# ledmatrix.net
KiCad netlist of a schematic drawn in EAGLE
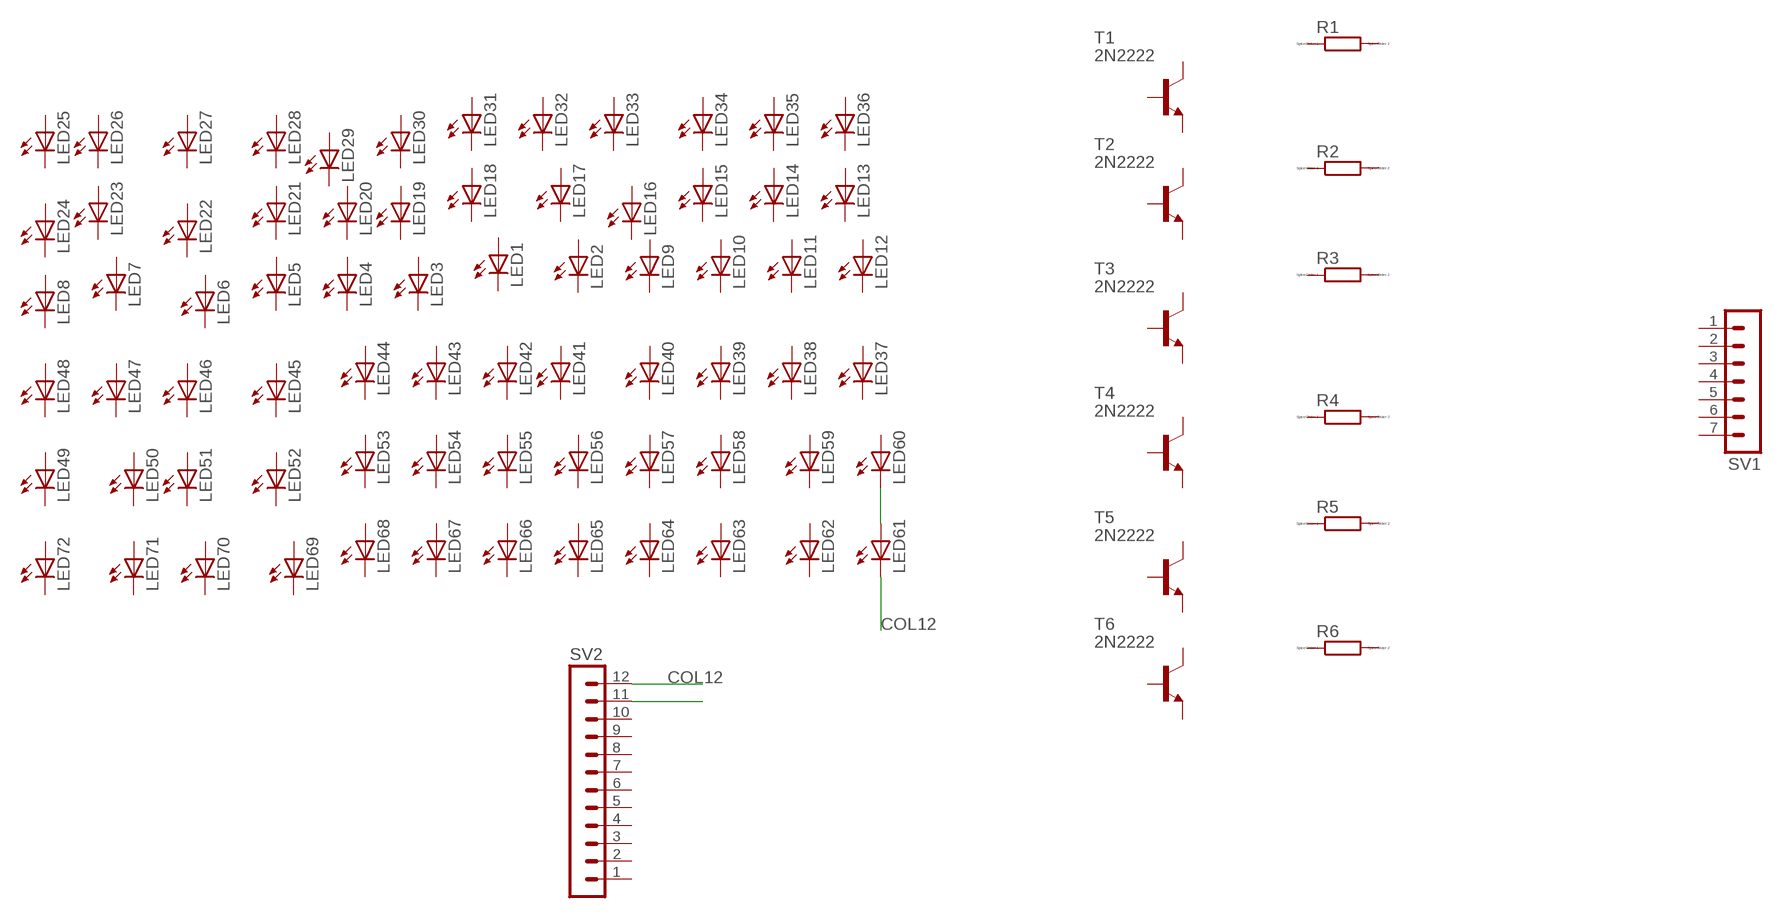
[diagram p0: schematic, sheet 1]

(export (version "E")
  (design (tool "Eeschema 10.0.6"))
  (components
    (comp (ref "LED1")
      (value "LED5MM")
      (footprint "eagle-import:LED5MM")
      (libsource (lib "eagle-import") (part "LED5MM"))
    )
    (comp (ref "LED2")
      (value "LED5MM")
      (footprint "eagle-import:LED5MM")
      (libsource (lib "eagle-import") (part "LED5MM"))
    )
    (comp (ref "LED3")
      (value "LED5MM")
      (footprint "eagle-import:LED5MM")
      (libsource (lib "eagle-import") (part "LED5MM"))
    )
    (comp (ref "LED4")
      (value "LED5MM")
      (footprint "eagle-import:LED5MM")
      (libsource (lib "eagle-import") (part "LED5MM"))
    )
    (comp (ref "LED5")
      (value "LED5MM")
      (footprint "eagle-import:LED5MM")
      (libsource (lib "eagle-import") (part "LED5MM"))
    )
    (comp (ref "LED6")
      (value "LED5MM")
      (footprint "eagle-import:LED5MM")
      (libsource (lib "eagle-import") (part "LED5MM"))
    )
    (comp (ref "LED7")
      (value "LED5MM")
      (footprint "eagle-import:LED5MM")
      (libsource (lib "eagle-import") (part "LED5MM"))
    )
    (comp (ref "LED8")
      (value "LED5MM")
      (footprint "eagle-import:LED5MM")
      (libsource (lib "eagle-import") (part "LED5MM"))
    )
    (comp (ref "LED9")
      (value "LED5MM")
      (footprint "eagle-import:LED5MM")
      (libsource (lib "eagle-import") (part "LED5MM"))
    )
    (comp (ref "LED10")
      (value "LED5MM")
      (footprint "eagle-import:LED5MM")
      (libsource (lib "eagle-import") (part "LED5MM"))
    )
    (comp (ref "LED11")
      (value "LED5MM")
      (footprint "eagle-import:LED5MM")
      (libsource (lib "eagle-import") (part "LED5MM"))
    )
    (comp (ref "LED12")
      (value "LED5MM")
      (footprint "eagle-import:LED5MM")
      (libsource (lib "eagle-import") (part "LED5MM"))
    )
    (comp (ref "LED13")
      (value "LED5MM")
      (footprint "eagle-import:LED5MM")
      (libsource (lib "eagle-import") (part "LED5MM"))
    )
    (comp (ref "LED14")
      (value "LED5MM")
      (footprint "eagle-import:LED5MM")
      (libsource (lib "eagle-import") (part "LED5MM"))
    )
    (comp (ref "LED15")
      (value "LED5MM")
      (footprint "eagle-import:LED5MM")
      (libsource (lib "eagle-import") (part "LED5MM"))
    )
    (comp (ref "LED16")
      (value "LED5MM")
      (footprint "eagle-import:LED5MM")
      (libsource (lib "eagle-import") (part "LED5MM"))
    )
    (comp (ref "LED17")
      (value "LED5MM")
      (footprint "eagle-import:LED5MM")
      (libsource (lib "eagle-import") (part "LED5MM"))
    )
    (comp (ref "LED18")
      (value "LED5MM")
      (footprint "eagle-import:LED5MM")
      (libsource (lib "eagle-import") (part "LED5MM"))
    )
    (comp (ref "LED19")
      (value "LED5MM")
      (footprint "eagle-import:LED5MM")
      (libsource (lib "eagle-import") (part "LED5MM"))
    )
    (comp (ref "LED20")
      (value "LED5MM")
      (footprint "eagle-import:LED5MM")
      (libsource (lib "eagle-import") (part "LED5MM"))
    )
    (comp (ref "LED21")
      (value "LED5MM")
      (footprint "eagle-import:LED5MM")
      (libsource (lib "eagle-import") (part "LED5MM"))
    )
    (comp (ref "LED22")
      (value "LED5MM")
      (footprint "eagle-import:LED5MM")
      (libsource (lib "eagle-import") (part "LED5MM"))
    )
    (comp (ref "LED23")
      (value "LED5MM")
      (footprint "eagle-import:LED5MM")
      (libsource (lib "eagle-import") (part "LED5MM"))
    )
    (comp (ref "LED24")
      (value "LED5MM")
      (footprint "eagle-import:LED5MM")
      (libsource (lib "eagle-import") (part "LED5MM"))
    )
    (comp (ref "LED25")
      (value "LED5MM")
      (footprint "eagle-import:LED5MM")
      (libsource (lib "eagle-import") (part "LED5MM"))
    )
    (comp (ref "LED26")
      (value "LED5MM")
      (footprint "eagle-import:LED5MM")
      (libsource (lib "eagle-import") (part "LED5MM"))
    )
    (comp (ref "LED27")
      (value "LED5MM")
      (footprint "eagle-import:LED5MM")
      (libsource (lib "eagle-import") (part "LED5MM"))
    )
    (comp (ref "LED28")
      (value "LED5MM")
      (footprint "eagle-import:LED5MM")
      (libsource (lib "eagle-import") (part "LED5MM"))
    )
    (comp (ref "LED29")
      (value "LED5MM")
      (footprint "eagle-import:LED5MM")
      (libsource (lib "eagle-import") (part "LED5MM"))
    )
    (comp (ref "LED30")
      (value "LED5MM")
      (footprint "eagle-import:LED5MM")
      (libsource (lib "eagle-import") (part "LED5MM"))
    )
    (comp (ref "LED31")
      (value "LED5MM")
      (footprint "eagle-import:LED5MM")
      (libsource (lib "eagle-import") (part "LED5MM"))
    )
    (comp (ref "LED32")
      (value "LED5MM")
      (footprint "eagle-import:LED5MM")
      (libsource (lib "eagle-import") (part "LED5MM"))
    )
    (comp (ref "LED33")
      (value "LED5MM")
      (footprint "eagle-import:LED5MM")
      (libsource (lib "eagle-import") (part "LED5MM"))
    )
    (comp (ref "LED34")
      (value "LED5MM")
      (footprint "eagle-import:LED5MM")
      (libsource (lib "eagle-import") (part "LED5MM"))
    )
    (comp (ref "LED35")
      (value "LED5MM")
      (footprint "eagle-import:LED5MM")
      (libsource (lib "eagle-import") (part "LED5MM"))
    )
    (comp (ref "LED36")
      (value "LED5MM")
      (footprint "eagle-import:LED5MM")
      (libsource (lib "eagle-import") (part "LED5MM"))
    )
    (comp (ref "LED37")
      (value "LED5MM")
      (footprint "eagle-import:LED5MM")
      (libsource (lib "eagle-import") (part "LED5MM"))
    )
    (comp (ref "LED38")
      (value "LED5MM")
      (footprint "eagle-import:LED5MM")
      (libsource (lib "eagle-import") (part "LED5MM"))
    )
    (comp (ref "LED39")
      (value "LED5MM")
      (footprint "eagle-import:LED5MM")
      (libsource (lib "eagle-import") (part "LED5MM"))
    )
    (comp (ref "LED40")
      (value "LED5MM")
      (footprint "eagle-import:LED5MM")
      (libsource (lib "eagle-import") (part "LED5MM"))
    )
    (comp (ref "LED41")
      (value "LED5MM")
      (footprint "eagle-import:LED5MM")
      (libsource (lib "eagle-import") (part "LED5MM"))
    )
    (comp (ref "LED42")
      (value "LED5MM")
      (footprint "eagle-import:LED5MM")
      (libsource (lib "eagle-import") (part "LED5MM"))
    )
    (comp (ref "LED43")
      (value "LED5MM")
      (footprint "eagle-import:LED5MM")
      (libsource (lib "eagle-import") (part "LED5MM"))
    )
    (comp (ref "LED44")
      (value "LED5MM")
      (footprint "eagle-import:LED5MM")
      (libsource (lib "eagle-import") (part "LED5MM"))
    )
    (comp (ref "LED45")
      (value "LED5MM")
      (footprint "eagle-import:LED5MM")
      (libsource (lib "eagle-import") (part "LED5MM"))
    )
    (comp (ref "LED46")
      (value "LED5MM")
      (footprint "eagle-import:LED5MM")
      (libsource (lib "eagle-import") (part "LED5MM"))
    )
    (comp (ref "LED47")
      (value "LED5MM")
      (footprint "eagle-import:LED5MM")
      (libsource (lib "eagle-import") (part "LED5MM"))
    )
    (comp (ref "LED48")
      (value "LED5MM")
      (footprint "eagle-import:LED5MM")
      (libsource (lib "eagle-import") (part "LED5MM"))
    )
    (comp (ref "LED49")
      (value "LED5MM")
      (footprint "eagle-import:LED5MM")
      (libsource (lib "eagle-import") (part "LED5MM"))
    )
    (comp (ref "LED50")
      (value "LED5MM")
      (footprint "eagle-import:LED5MM")
      (libsource (lib "eagle-import") (part "LED5MM"))
    )
    (comp (ref "LED51")
      (value "LED5MM")
      (footprint "eagle-import:LED5MM")
      (libsource (lib "eagle-import") (part "LED5MM"))
    )
    (comp (ref "LED52")
      (value "LED5MM")
      (footprint "eagle-import:LED5MM")
      (libsource (lib "eagle-import") (part "LED5MM"))
    )
    (comp (ref "LED53")
      (value "LED5MM")
      (footprint "eagle-import:LED5MM")
      (libsource (lib "eagle-import") (part "LED5MM"))
    )
    (comp (ref "LED54")
      (value "LED5MM")
      (footprint "eagle-import:LED5MM")
      (libsource (lib "eagle-import") (part "LED5MM"))
    )
    (comp (ref "LED55")
      (value "LED5MM")
      (footprint "eagle-import:LED5MM")
      (libsource (lib "eagle-import") (part "LED5MM"))
    )
    (comp (ref "LED56")
      (value "LED5MM")
      (footprint "eagle-import:LED5MM")
      (libsource (lib "eagle-import") (part "LED5MM"))
    )
    (comp (ref "LED57")
      (value "LED5MM")
      (footprint "eagle-import:LED5MM")
      (libsource (lib "eagle-import") (part "LED5MM"))
    )
    (comp (ref "LED58")
      (value "LED5MM")
      (footprint "eagle-import:LED5MM")
      (libsource (lib "eagle-import") (part "LED5MM"))
    )
    (comp (ref "LED59")
      (value "LED5MM")
      (footprint "eagle-import:LED5MM")
      (libsource (lib "eagle-import") (part "LED5MM"))
    )
    (comp (ref "LED60")
      (value "LED5MM")
      (footprint "eagle-import:LED5MM")
      (libsource (lib "eagle-import") (part "LED5MM"))
    )
    (comp (ref "LED61")
      (value "LED5MM")
      (footprint "eagle-import:LED5MM")
      (libsource (lib "eagle-import") (part "LED5MM"))
    )
    (comp (ref "LED62")
      (value "LED5MM")
      (footprint "eagle-import:LED5MM")
      (libsource (lib "eagle-import") (part "LED5MM"))
    )
    (comp (ref "LED63")
      (value "LED5MM")
      (footprint "eagle-import:LED5MM")
      (libsource (lib "eagle-import") (part "LED5MM"))
    )
    (comp (ref "LED64")
      (value "LED5MM")
      (footprint "eagle-import:LED5MM")
      (libsource (lib "eagle-import") (part "LED5MM"))
    )
    (comp (ref "LED65")
      (value "LED5MM")
      (footprint "eagle-import:LED5MM")
      (libsource (lib "eagle-import") (part "LED5MM"))
    )
    (comp (ref "LED66")
      (value "LED5MM")
      (footprint "eagle-import:LED5MM")
      (libsource (lib "eagle-import") (part "LED5MM"))
    )
    (comp (ref "LED67")
      (value "LED5MM")
      (footprint "eagle-import:LED5MM")
      (libsource (lib "eagle-import") (part "LED5MM"))
    )
    (comp (ref "LED68")
      (value "LED5MM")
      (footprint "eagle-import:LED5MM")
      (libsource (lib "eagle-import") (part "LED5MM"))
    )
    (comp (ref "LED69")
      (value "LED5MM")
      (footprint "eagle-import:LED5MM")
      (libsource (lib "eagle-import") (part "LED5MM"))
    )
    (comp (ref "LED70")
      (value "LED5MM")
      (footprint "eagle-import:LED5MM")
      (libsource (lib "eagle-import") (part "LED5MM"))
    )
    (comp (ref "LED71")
      (value "LED5MM")
      (footprint "eagle-import:LED5MM")
      (libsource (lib "eagle-import") (part "LED5MM"))
    )
    (comp (ref "LED72")
      (value "LED5MM")
      (footprint "eagle-import:LED5MM")
      (libsource (lib "eagle-import") (part "LED5MM"))
    )
    (comp (ref "R1")
      (value "R0204/7")
      (footprint "eagle-import:0204_7")
      (libsource (lib "eagle-import") (part "R0204/7"))
    )
    (comp (ref "R2")
      (value "R0204/7")
      (footprint "eagle-import:0204_7")
      (libsource (lib "eagle-import") (part "R0204/7"))
    )
    (comp (ref "R3")
      (value "R0204/7")
      (footprint "eagle-import:0204_7")
      (libsource (lib "eagle-import") (part "R0204/7"))
    )
    (comp (ref "R4")
      (value "R0204/7")
      (footprint "eagle-import:0204_7")
      (libsource (lib "eagle-import") (part "R0204/7"))
    )
    (comp (ref "R5")
      (value "R0204/7")
      (footprint "eagle-import:0204_7")
      (libsource (lib "eagle-import") (part "R0204/7"))
    )
    (comp (ref "R6")
      (value "R0204/7")
      (footprint "eagle-import:0204_7")
      (libsource (lib "eagle-import") (part "R0204/7"))
    )
    (comp (ref "SV1")
      (value "MA07-1")
      (footprint "eagle-import:MA07-1")
      (libsource (lib "eagle-import") (part "MA07-1"))
    )
    (comp (ref "SV2")
      (value "MA12-1")
      (footprint "eagle-import:MA12-1")
      (libsource (lib "eagle-import") (part "MA12-1"))
    )
    (comp (ref "T1")
      (value "2N2222")
      (footprint "eagle-import:TO18")
      (libsource (lib "eagle-import") (part "2N2222"))
    )
    (comp (ref "T2")
      (value "2N2222")
      (footprint "eagle-import:TO18")
      (libsource (lib "eagle-import") (part "2N2222"))
    )
    (comp (ref "T3")
      (value "2N2222")
      (footprint "eagle-import:TO18")
      (libsource (lib "eagle-import") (part "2N2222"))
    )
    (comp (ref "T4")
      (value "2N2222")
      (footprint "eagle-import:TO18")
      (libsource (lib "eagle-import") (part "2N2222"))
    )
    (comp (ref "T5")
      (value "2N2222")
      (footprint "eagle-import:TO18")
      (libsource (lib "eagle-import") (part "2N2222"))
    )
    (comp (ref "T6")
      (value "2N2222")
      (footprint "eagle-import:TO18")
      (libsource (lib "eagle-import") (part "2N2222"))
    )
  )
  (nets
    (net (code "1") (name "/COL12") (class "Default")
      (node (ref "LED61") (pin "K") (pinfunction "C_K") (pintype "passive"))
      (node (ref "SV2") (pin "12") (pinfunction "12_12") (pintype "passive"))
    )
    (net (code "2") (name "Net-(LED60-C)") (class "Default")
      (node (ref "LED60") (pin "K") (pinfunction "C_K") (pintype "passive"))
      (node (ref "LED61") (pin "A") (pinfunction "A_A") (pintype "passive"))
    )
    (net (code "3") (name "unconnected-(LED1-C-PadK)") (class "Default")
      (node (ref "LED1") (pin "K") (pinfunction "C_K") (pintype "passive"))
    )
    (net (code "4") (name "unconnected-(LED1-PadA)") (class "Default")
      (node (ref "LED1") (pin "A") (pinfunction "A_A") (pintype "passive"))
    )
    (net (code "5") (name "unconnected-(LED2-C-PadK)") (class "Default")
      (node (ref "LED2") (pin "K") (pinfunction "C_K") (pintype "passive"))
    )
    (net (code "6") (name "unconnected-(LED2-PadA)") (class "Default")
      (node (ref "LED2") (pin "A") (pinfunction "A_A") (pintype "passive"))
    )
    (net (code "7") (name "unconnected-(LED3-C-PadK)") (class "Default")
      (node (ref "LED3") (pin "K") (pinfunction "C_K") (pintype "passive"))
    )
    (net (code "8") (name "unconnected-(LED3-PadA)") (class "Default")
      (node (ref "LED3") (pin "A") (pinfunction "A_A") (pintype "passive"))
    )
    (net (code "9") (name "unconnected-(LED4-C-PadK)") (class "Default")
      (node (ref "LED4") (pin "K") (pinfunction "C_K") (pintype "passive"))
    )
    (net (code "10") (name "unconnected-(LED4-PadA)") (class "Default")
      (node (ref "LED4") (pin "A") (pinfunction "A_A") (pintype "passive"))
    )
    (net (code "11") (name "unconnected-(LED5-C-PadK)") (class "Default")
      (node (ref "LED5") (pin "K") (pinfunction "C_K") (pintype "passive"))
    )
    (net (code "12") (name "unconnected-(LED5-PadA)") (class "Default")
      (node (ref "LED5") (pin "A") (pinfunction "A_A") (pintype "passive"))
    )
    (net (code "13") (name "unconnected-(LED6-C-PadK)") (class "Default")
      (node (ref "LED6") (pin "K") (pinfunction "C_K") (pintype "passive"))
    )
    (net (code "14") (name "unconnected-(LED6-PadA)") (class "Default")
      (node (ref "LED6") (pin "A") (pinfunction "A_A") (pintype "passive"))
    )
    (net (code "15") (name "unconnected-(LED7-C-PadK)") (class "Default")
      (node (ref "LED7") (pin "K") (pinfunction "C_K") (pintype "passive"))
    )
    (net (code "16") (name "unconnected-(LED7-PadA)") (class "Default")
      (node (ref "LED7") (pin "A") (pinfunction "A_A") (pintype "passive"))
    )
    (net (code "17") (name "unconnected-(LED8-C-PadK)") (class "Default")
      (node (ref "LED8") (pin "K") (pinfunction "C_K") (pintype "passive"))
    )
    (net (code "18") (name "unconnected-(LED8-PadA)") (class "Default")
      (node (ref "LED8") (pin "A") (pinfunction "A_A") (pintype "passive"))
    )
    (net (code "19") (name "unconnected-(LED9-C-PadK)") (class "Default")
      (node (ref "LED9") (pin "K") (pinfunction "C_K") (pintype "passive"))
    )
    (net (code "20") (name "unconnected-(LED9-PadA)") (class "Default")
      (node (ref "LED9") (pin "A") (pinfunction "A_A") (pintype "passive"))
    )
    (net (code "21") (name "unconnected-(LED10-C-PadK)") (class "Default")
      (node (ref "LED10") (pin "K") (pinfunction "C_K") (pintype "passive"))
    )
    (net (code "22") (name "unconnected-(LED10-PadA)") (class "Default")
      (node (ref "LED10") (pin "A") (pinfunction "A_A") (pintype "passive"))
    )
    (net (code "23") (name "unconnected-(LED11-C-PadK)") (class "Default")
      (node (ref "LED11") (pin "K") (pinfunction "C_K") (pintype "passive"))
    )
    (net (code "24") (name "unconnected-(LED11-PadA)") (class "Default")
      (node (ref "LED11") (pin "A") (pinfunction "A_A") (pintype "passive"))
    )
    (net (code "25") (name "unconnected-(LED12-C-PadK)") (class "Default")
      (node (ref "LED12") (pin "K") (pinfunction "C_K") (pintype "passive"))
    )
    (net (code "26") (name "unconnected-(LED12-PadA)") (class "Default")
      (node (ref "LED12") (pin "A") (pinfunction "A_A") (pintype "passive"))
    )
    (net (code "27") (name "unconnected-(LED13-C-PadK)") (class "Default")
      (node (ref "LED13") (pin "K") (pinfunction "C_K") (pintype "passive"))
    )
    (net (code "28") (name "unconnected-(LED13-PadA)") (class "Default")
      (node (ref "LED13") (pin "A") (pinfunction "A_A") (pintype "passive"))
    )
    (net (code "29") (name "unconnected-(LED14-C-PadK)") (class "Default")
      (node (ref "LED14") (pin "K") (pinfunction "C_K") (pintype "passive"))
    )
    (net (code "30") (name "unconnected-(LED14-PadA)") (class "Default")
      (node (ref "LED14") (pin "A") (pinfunction "A_A") (pintype "passive"))
    )
    (net (code "31") (name "unconnected-(LED15-C-PadK)") (class "Default")
      (node (ref "LED15") (pin "K") (pinfunction "C_K") (pintype "passive"))
    )
    (net (code "32") (name "unconnected-(LED15-PadA)") (class "Default")
      (node (ref "LED15") (pin "A") (pinfunction "A_A") (pintype "passive"))
    )
    (net (code "33") (name "unconnected-(LED16-C-PadK)") (class "Default")
      (node (ref "LED16") (pin "K") (pinfunction "C_K") (pintype "passive"))
    )
    (net (code "34") (name "unconnected-(LED16-PadA)") (class "Default")
      (node (ref "LED16") (pin "A") (pinfunction "A_A") (pintype "passive"))
    )
    (net (code "35") (name "unconnected-(LED17-C-PadK)") (class "Default")
      (node (ref "LED17") (pin "K") (pinfunction "C_K") (pintype "passive"))
    )
    (net (code "36") (name "unconnected-(LED17-PadA)") (class "Default")
      (node (ref "LED17") (pin "A") (pinfunction "A_A") (pintype "passive"))
    )
    (net (code "37") (name "unconnected-(LED18-C-PadK)") (class "Default")
      (node (ref "LED18") (pin "K") (pinfunction "C_K") (pintype "passive"))
    )
    (net (code "38") (name "unconnected-(LED18-PadA)") (class "Default")
      (node (ref "LED18") (pin "A") (pinfunction "A_A") (pintype "passive"))
    )
    (net (code "39") (name "unconnected-(LED19-C-PadK)") (class "Default")
      (node (ref "LED19") (pin "K") (pinfunction "C_K") (pintype "passive"))
    )
    (net (code "40") (name "unconnected-(LED19-PadA)") (class "Default")
      (node (ref "LED19") (pin "A") (pinfunction "A_A") (pintype "passive"))
    )
    (net (code "41") (name "unconnected-(LED20-C-PadK)") (class "Default")
      (node (ref "LED20") (pin "K") (pinfunction "C_K") (pintype "passive"))
    )
    (net (code "42") (name "unconnected-(LED20-PadA)") (class "Default")
      (node (ref "LED20") (pin "A") (pinfunction "A_A") (pintype "passive"))
    )
    (net (code "43") (name "unconnected-(LED21-C-PadK)") (class "Default")
      (node (ref "LED21") (pin "K") (pinfunction "C_K") (pintype "passive"))
    )
    (net (code "44") (name "unconnected-(LED21-PadA)") (class "Default")
      (node (ref "LED21") (pin "A") (pinfunction "A_A") (pintype "passive"))
    )
    (net (code "45") (name "unconnected-(LED22-C-PadK)") (class "Default")
      (node (ref "LED22") (pin "K") (pinfunction "C_K") (pintype "passive"))
    )
    (net (code "46") (name "unconnected-(LED22-PadA)") (class "Default")
      (node (ref "LED22") (pin "A") (pinfunction "A_A") (pintype "passive"))
    )
    (net (code "47") (name "unconnected-(LED23-C-PadK)") (class "Default")
      (node (ref "LED23") (pin "K") (pinfunction "C_K") (pintype "passive"))
    )
    (net (code "48") (name "unconnected-(LED23-PadA)") (class "Default")
      (node (ref "LED23") (pin "A") (pinfunction "A_A") (pintype "passive"))
    )
    (net (code "49") (name "unconnected-(LED24-C-PadK)") (class "Default")
      (node (ref "LED24") (pin "K") (pinfunction "C_K") (pintype "passive"))
    )
    (net (code "50") (name "unconnected-(LED24-PadA)") (class "Default")
      (node (ref "LED24") (pin "A") (pinfunction "A_A") (pintype "passive"))
    )
    (net (code "51") (name "unconnected-(LED25-C-PadK)") (class "Default")
      (node (ref "LED25") (pin "K") (pinfunction "C_K") (pintype "passive"))
    )
    (net (code "52") (name "unconnected-(LED25-PadA)") (class "Default")
      (node (ref "LED25") (pin "A") (pinfunction "A_A") (pintype "passive"))
    )
    (net (code "53") (name "unconnected-(LED26-C-PadK)") (class "Default")
      (node (ref "LED26") (pin "K") (pinfunction "C_K") (pintype "passive"))
    )
    (net (code "54") (name "unconnected-(LED26-PadA)") (class "Default")
      (node (ref "LED26") (pin "A") (pinfunction "A_A") (pintype "passive"))
    )
    (net (code "55") (name "unconnected-(LED27-C-PadK)") (class "Default")
      (node (ref "LED27") (pin "K") (pinfunction "C_K") (pintype "passive"))
    )
    (net (code "56") (name "unconnected-(LED27-PadA)") (class "Default")
      (node (ref "LED27") (pin "A") (pinfunction "A_A") (pintype "passive"))
    )
    (net (code "57") (name "unconnected-(LED28-C-PadK)") (class "Default")
      (node (ref "LED28") (pin "K") (pinfunction "C_K") (pintype "passive"))
    )
    (net (code "58") (name "unconnected-(LED28-PadA)") (class "Default")
      (node (ref "LED28") (pin "A") (pinfunction "A_A") (pintype "passive"))
    )
    (net (code "59") (name "unconnected-(LED29-C-PadK)") (class "Default")
      (node (ref "LED29") (pin "K") (pinfunction "C_K") (pintype "passive"))
    )
    (net (code "60") (name "unconnected-(LED29-PadA)") (class "Default")
      (node (ref "LED29") (pin "A") (pinfunction "A_A") (pintype "passive"))
    )
    (net (code "61") (name "unconnected-(LED30-C-PadK)") (class "Default")
      (node (ref "LED30") (pin "K") (pinfunction "C_K") (pintype "passive"))
    )
    (net (code "62") (name "unconnected-(LED30-PadA)") (class "Default")
      (node (ref "LED30") (pin "A") (pinfunction "A_A") (pintype "passive"))
    )
    (net (code "63") (name "unconnected-(LED31-C-PadK)") (class "Default")
      (node (ref "LED31") (pin "K") (pinfunction "C_K") (pintype "passive"))
    )
    (net (code "64") (name "unconnected-(LED31-PadA)") (class "Default")
      (node (ref "LED31") (pin "A") (pinfunction "A_A") (pintype "passive"))
    )
    (net (code "65") (name "unconnected-(LED32-C-PadK)") (class "Default")
      (node (ref "LED32") (pin "K") (pinfunction "C_K") (pintype "passive"))
    )
    (net (code "66") (name "unconnected-(LED32-PadA)") (class "Default")
      (node (ref "LED32") (pin "A") (pinfunction "A_A") (pintype "passive"))
    )
    (net (code "67") (name "unconnected-(LED33-C-PadK)") (class "Default")
      (node (ref "LED33") (pin "K") (pinfunction "C_K") (pintype "passive"))
    )
    (net (code "68") (name "unconnected-(LED33-PadA)") (class "Default")
      (node (ref "LED33") (pin "A") (pinfunction "A_A") (pintype "passive"))
    )
    (net (code "69") (name "unconnected-(LED34-C-PadK)") (class "Default")
      (node (ref "LED34") (pin "K") (pinfunction "C_K") (pintype "passive"))
    )
    (net (code "70") (name "unconnected-(LED34-PadA)") (class "Default")
      (node (ref "LED34") (pin "A") (pinfunction "A_A") (pintype "passive"))
    )
    (net (code "71") (name "unconnected-(LED35-C-PadK)") (class "Default")
      (node (ref "LED35") (pin "K") (pinfunction "C_K") (pintype "passive"))
    )
    (net (code "72") (name "unconnected-(LED35-PadA)") (class "Default")
      (node (ref "LED35") (pin "A") (pinfunction "A_A") (pintype "passive"))
    )
    (net (code "73") (name "unconnected-(LED36-C-PadK)") (class "Default")
      (node (ref "LED36") (pin "K") (pinfunction "C_K") (pintype "passive"))
    )
    (net (code "74") (name "unconnected-(LED36-PadA)") (class "Default")
      (node (ref "LED36") (pin "A") (pinfunction "A_A") (pintype "passive"))
    )
    (net (code "75") (name "unconnected-(LED37-C-PadK)") (class "Default")
      (node (ref "LED37") (pin "K") (pinfunction "C_K") (pintype "passive"))
    )
    (net (code "76") (name "unconnected-(LED37-PadA)") (class "Default")
      (node (ref "LED37") (pin "A") (pinfunction "A_A") (pintype "passive"))
    )
    (net (code "77") (name "unconnected-(LED38-C-PadK)") (class "Default")
      (node (ref "LED38") (pin "K") (pinfunction "C_K") (pintype "passive"))
    )
    (net (code "78") (name "unconnected-(LED38-PadA)") (class "Default")
      (node (ref "LED38") (pin "A") (pinfunction "A_A") (pintype "passive"))
    )
    (net (code "79") (name "unconnected-(LED39-C-PadK)") (class "Default")
      (node (ref "LED39") (pin "K") (pinfunction "C_K") (pintype "passive"))
    )
    (net (code "80") (name "unconnected-(LED39-PadA)") (class "Default")
      (node (ref "LED39") (pin "A") (pinfunction "A_A") (pintype "passive"))
    )
    (net (code "81") (name "unconnected-(LED40-C-PadK)") (class "Default")
      (node (ref "LED40") (pin "K") (pinfunction "C_K") (pintype "passive"))
    )
    (net (code "82") (name "unconnected-(LED40-PadA)") (class "Default")
      (node (ref "LED40") (pin "A") (pinfunction "A_A") (pintype "passive"))
    )
    (net (code "83") (name "unconnected-(LED41-C-PadK)") (class "Default")
      (node (ref "LED41") (pin "K") (pinfunction "C_K") (pintype "passive"))
    )
    (net (code "84") (name "unconnected-(LED41-PadA)") (class "Default")
      (node (ref "LED41") (pin "A") (pinfunction "A_A") (pintype "passive"))
    )
    (net (code "85") (name "unconnected-(LED42-C-PadK)") (class "Default")
      (node (ref "LED42") (pin "K") (pinfunction "C_K") (pintype "passive"))
    )
    (net (code "86") (name "unconnected-(LED42-PadA)") (class "Default")
      (node (ref "LED42") (pin "A") (pinfunction "A_A") (pintype "passive"))
    )
    (net (code "87") (name "unconnected-(LED43-C-PadK)") (class "Default")
      (node (ref "LED43") (pin "K") (pinfunction "C_K") (pintype "passive"))
    )
    (net (code "88") (name "unconnected-(LED43-PadA)") (class "Default")
      (node (ref "LED43") (pin "A") (pinfunction "A_A") (pintype "passive"))
    )
    (net (code "89") (name "unconnected-(LED44-C-PadK)") (class "Default")
      (node (ref "LED44") (pin "K") (pinfunction "C_K") (pintype "passive"))
    )
    (net (code "90") (name "unconnected-(LED44-PadA)") (class "Default")
      (node (ref "LED44") (pin "A") (pinfunction "A_A") (pintype "passive"))
    )
    (net (code "91") (name "unconnected-(LED45-C-PadK)") (class "Default")
      (node (ref "LED45") (pin "K") (pinfunction "C_K") (pintype "passive"))
    )
    (net (code "92") (name "unconnected-(LED45-PadA)") (class "Default")
      (node (ref "LED45") (pin "A") (pinfunction "A_A") (pintype "passive"))
    )
    (net (code "93") (name "unconnected-(LED46-C-PadK)") (class "Default")
      (node (ref "LED46") (pin "K") (pinfunction "C_K") (pintype "passive"))
    )
    (net (code "94") (name "unconnected-(LED46-PadA)") (class "Default")
      (node (ref "LED46") (pin "A") (pinfunction "A_A") (pintype "passive"))
    )
    (net (code "95") (name "unconnected-(LED47-C-PadK)") (class "Default")
      (node (ref "LED47") (pin "K") (pinfunction "C_K") (pintype "passive"))
    )
    (net (code "96") (name "unconnected-(LED47-PadA)") (class "Default")
      (node (ref "LED47") (pin "A") (pinfunction "A_A") (pintype "passive"))
    )
    (net (code "97") (name "unconnected-(LED48-C-PadK)") (class "Default")
      (node (ref "LED48") (pin "K") (pinfunction "C_K") (pintype "passive"))
    )
    (net (code "98") (name "unconnected-(LED48-PadA)") (class "Default")
      (node (ref "LED48") (pin "A") (pinfunction "A_A") (pintype "passive"))
    )
    (net (code "99") (name "unconnected-(LED49-C-PadK)") (class "Default")
      (node (ref "LED49") (pin "K") (pinfunction "C_K") (pintype "passive"))
    )
    (net (code "100") (name "unconnected-(LED49-PadA)") (class "Default")
      (node (ref "LED49") (pin "A") (pinfunction "A_A") (pintype "passive"))
    )
    (net (code "101") (name "unconnected-(LED50-C-PadK)") (class "Default")
      (node (ref "LED50") (pin "K") (pinfunction "C_K") (pintype "passive"))
    )
    (net (code "102") (name "unconnected-(LED50-PadA)") (class "Default")
      (node (ref "LED50") (pin "A") (pinfunction "A_A") (pintype "passive"))
    )
    (net (code "103") (name "unconnected-(LED51-C-PadK)") (class "Default")
      (node (ref "LED51") (pin "K") (pinfunction "C_K") (pintype "passive"))
    )
    (net (code "104") (name "unconnected-(LED51-PadA)") (class "Default")
      (node (ref "LED51") (pin "A") (pinfunction "A_A") (pintype "passive"))
    )
    (net (code "105") (name "unconnected-(LED52-C-PadK)") (class "Default")
      (node (ref "LED52") (pin "K") (pinfunction "C_K") (pintype "passive"))
    )
    (net (code "106") (name "unconnected-(LED52-PadA)") (class "Default")
      (node (ref "LED52") (pin "A") (pinfunction "A_A") (pintype "passive"))
    )
    (net (code "107") (name "unconnected-(LED53-C-PadK)") (class "Default")
      (node (ref "LED53") (pin "K") (pinfunction "C_K") (pintype "passive"))
    )
    (net (code "108") (name "unconnected-(LED53-PadA)") (class "Default")
      (node (ref "LED53") (pin "A") (pinfunction "A_A") (pintype "passive"))
    )
    (net (code "109") (name "unconnected-(LED54-C-PadK)") (class "Default")
      (node (ref "LED54") (pin "K") (pinfunction "C_K") (pintype "passive"))
    )
    (net (code "110") (name "unconnected-(LED54-PadA)") (class "Default")
      (node (ref "LED54") (pin "A") (pinfunction "A_A") (pintype "passive"))
    )
    (net (code "111") (name "unconnected-(LED55-C-PadK)") (class "Default")
      (node (ref "LED55") (pin "K") (pinfunction "C_K") (pintype "passive"))
    )
    (net (code "112") (name "unconnected-(LED55-PadA)") (class "Default")
      (node (ref "LED55") (pin "A") (pinfunction "A_A") (pintype "passive"))
    )
    (net (code "113") (name "unconnected-(LED56-C-PadK)") (class "Default")
      (node (ref "LED56") (pin "K") (pinfunction "C_K") (pintype "passive"))
    )
    (net (code "114") (name "unconnected-(LED56-PadA)") (class "Default")
      (node (ref "LED56") (pin "A") (pinfunction "A_A") (pintype "passive"))
    )
    (net (code "115") (name "unconnected-(LED57-C-PadK)") (class "Default")
      (node (ref "LED57") (pin "K") (pinfunction "C_K") (pintype "passive"))
    )
    (net (code "116") (name "unconnected-(LED57-PadA)") (class "Default")
      (node (ref "LED57") (pin "A") (pinfunction "A_A") (pintype "passive"))
    )
    (net (code "117") (name "unconnected-(LED58-C-PadK)") (class "Default")
      (node (ref "LED58") (pin "K") (pinfunction "C_K") (pintype "passive"))
    )
    (net (code "118") (name "unconnected-(LED58-PadA)") (class "Default")
      (node (ref "LED58") (pin "A") (pinfunction "A_A") (pintype "passive"))
    )
    (net (code "119") (name "unconnected-(LED59-C-PadK)") (class "Default")
      (node (ref "LED59") (pin "K") (pinfunction "C_K") (pintype "passive"))
    )
    (net (code "120") (name "unconnected-(LED59-PadA)") (class "Default")
      (node (ref "LED59") (pin "A") (pinfunction "A_A") (pintype "passive"))
    )
    (net (code "121") (name "unconnected-(LED60-PadA)") (class "Default")
      (node (ref "LED60") (pin "A") (pinfunction "A_A") (pintype "passive"))
    )
    (net (code "122") (name "unconnected-(LED62-C-PadK)") (class "Default")
      (node (ref "LED62") (pin "K") (pinfunction "C_K") (pintype "passive"))
    )
    (net (code "123") (name "unconnected-(LED62-PadA)") (class "Default")
      (node (ref "LED62") (pin "A") (pinfunction "A_A") (pintype "passive"))
    )
    (net (code "124") (name "unconnected-(LED63-C-PadK)") (class "Default")
      (node (ref "LED63") (pin "K") (pinfunction "C_K") (pintype "passive"))
    )
    (net (code "125") (name "unconnected-(LED63-PadA)") (class "Default")
      (node (ref "LED63") (pin "A") (pinfunction "A_A") (pintype "passive"))
    )
    (net (code "126") (name "unconnected-(LED64-C-PadK)") (class "Default")
      (node (ref "LED64") (pin "K") (pinfunction "C_K") (pintype "passive"))
    )
    (net (code "127") (name "unconnected-(LED64-PadA)") (class "Default")
      (node (ref "LED64") (pin "A") (pinfunction "A_A") (pintype "passive"))
    )
    (net (code "128") (name "unconnected-(LED65-C-PadK)") (class "Default")
      (node (ref "LED65") (pin "K") (pinfunction "C_K") (pintype "passive"))
    )
    (net (code "129") (name "unconnected-(LED65-PadA)") (class "Default")
      (node (ref "LED65") (pin "A") (pinfunction "A_A") (pintype "passive"))
    )
    (net (code "130") (name "unconnected-(LED66-C-PadK)") (class "Default")
      (node (ref "LED66") (pin "K") (pinfunction "C_K") (pintype "passive"))
    )
    (net (code "131") (name "unconnected-(LED66-PadA)") (class "Default")
      (node (ref "LED66") (pin "A") (pinfunction "A_A") (pintype "passive"))
    )
    (net (code "132") (name "unconnected-(LED67-C-PadK)") (class "Default")
      (node (ref "LED67") (pin "K") (pinfunction "C_K") (pintype "passive"))
    )
    (net (code "133") (name "unconnected-(LED67-PadA)") (class "Default")
      (node (ref "LED67") (pin "A") (pinfunction "A_A") (pintype "passive"))
    )
    (net (code "134") (name "unconnected-(LED68-C-PadK)") (class "Default")
      (node (ref "LED68") (pin "K") (pinfunction "C_K") (pintype "passive"))
    )
    (net (code "135") (name "unconnected-(LED68-PadA)") (class "Default")
      (node (ref "LED68") (pin "A") (pinfunction "A_A") (pintype "passive"))
    )
    (net (code "136") (name "unconnected-(LED69-C-PadK)") (class "Default")
      (node (ref "LED69") (pin "K") (pinfunction "C_K") (pintype "passive"))
    )
    (net (code "137") (name "unconnected-(LED69-PadA)") (class "Default")
      (node (ref "LED69") (pin "A") (pinfunction "A_A") (pintype "passive"))
    )
    (net (code "138") (name "unconnected-(LED70-C-PadK)") (class "Default")
      (node (ref "LED70") (pin "K") (pinfunction "C_K") (pintype "passive"))
    )
    (net (code "139") (name "unconnected-(LED70-PadA)") (class "Default")
      (node (ref "LED70") (pin "A") (pinfunction "A_A") (pintype "passive"))
    )
    (net (code "140") (name "unconnected-(LED71-C-PadK)") (class "Default")
      (node (ref "LED71") (pin "K") (pinfunction "C_K") (pintype "passive"))
    )
    (net (code "141") (name "unconnected-(LED71-PadA)") (class "Default")
      (node (ref "LED71") (pin "A") (pinfunction "A_A") (pintype "passive"))
    )
    (net (code "142") (name "unconnected-(LED72-C-PadK)") (class "Default")
      (node (ref "LED72") (pin "K") (pinfunction "C_K") (pintype "passive"))
    )
    (net (code "143") (name "unconnected-(LED72-PadA)") (class "Default")
      (node (ref "LED72") (pin "A") (pinfunction "A_A") (pintype "passive"))
    )
    (net (code "144") (name "unconnected-(R1-Pad1)") (class "Default")
      (node (ref "R1") (pin "1") (pinfunction "1_1") (pintype "passive"))
    )
    (net (code "145") (name "unconnected-(R1-Pad2)") (class "Default")
      (node (ref "R1") (pin "2") (pinfunction "2_2") (pintype "passive"))
    )
    (net (code "146") (name "unconnected-(R2-Pad1)") (class "Default")
      (node (ref "R2") (pin "1") (pinfunction "1_1") (pintype "passive"))
    )
    (net (code "147") (name "unconnected-(R2-Pad2)") (class "Default")
      (node (ref "R2") (pin "2") (pinfunction "2_2") (pintype "passive"))
    )
    (net (code "148") (name "unconnected-(R3-Pad1)") (class "Default")
      (node (ref "R3") (pin "1") (pinfunction "1_1") (pintype "passive"))
    )
    (net (code "149") (name "unconnected-(R3-Pad2)") (class "Default")
      (node (ref "R3") (pin "2") (pinfunction "2_2") (pintype "passive"))
    )
    (net (code "150") (name "unconnected-(R4-Pad1)") (class "Default")
      (node (ref "R4") (pin "1") (pinfunction "1_1") (pintype "passive"))
    )
    (net (code "151") (name "unconnected-(R4-Pad2)") (class "Default")
      (node (ref "R4") (pin "2") (pinfunction "2_2") (pintype "passive"))
    )
    (net (code "152") (name "unconnected-(R5-Pad1)") (class "Default")
      (node (ref "R5") (pin "1") (pinfunction "1_1") (pintype "passive"))
    )
    (net (code "153") (name "unconnected-(R5-Pad2)") (class "Default")
      (node (ref "R5") (pin "2") (pinfunction "2_2") (pintype "passive"))
    )
    (net (code "154") (name "unconnected-(R6-Pad1)") (class "Default")
      (node (ref "R6") (pin "1") (pinfunction "1_1") (pintype "passive"))
    )
    (net (code "155") (name "unconnected-(R6-Pad2)") (class "Default")
      (node (ref "R6") (pin "2") (pinfunction "2_2") (pintype "passive"))
    )
    (net (code "156") (name "unconnected-(SV1-Pad1)") (class "Default")
      (node (ref "SV1") (pin "1") (pinfunction "1_1") (pintype "passive"))
    )
    (net (code "157") (name "unconnected-(SV1-Pad2)") (class "Default")
      (node (ref "SV1") (pin "2") (pinfunction "2_2") (pintype "passive"))
    )
    (net (code "158") (name "unconnected-(SV1-Pad3)") (class "Default")
      (node (ref "SV1") (pin "3") (pinfunction "3_3") (pintype "passive"))
    )
    (net (code "159") (name "unconnected-(SV1-Pad4)") (class "Default")
      (node (ref "SV1") (pin "4") (pinfunction "4_4") (pintype "passive"))
    )
    (net (code "160") (name "unconnected-(SV1-Pad5)") (class "Default")
      (node (ref "SV1") (pin "5") (pinfunction "5_5") (pintype "passive"))
    )
    (net (code "161") (name "unconnected-(SV1-Pad6)") (class "Default")
      (node (ref "SV1") (pin "6") (pinfunction "6_6") (pintype "passive"))
    )
    (net (code "162") (name "unconnected-(SV1-Pad7)") (class "Default")
      (node (ref "SV1") (pin "7") (pinfunction "7_7") (pintype "passive"))
    )
    (net (code "163") (name "unconnected-(SV2-Pad1)") (class "Default")
      (node (ref "SV2") (pin "1") (pinfunction "1_1") (pintype "passive"))
    )
    (net (code "164") (name "unconnected-(SV2-Pad2)") (class "Default")
      (node (ref "SV2") (pin "2") (pinfunction "2_2") (pintype "passive"))
    )
    (net (code "165") (name "unconnected-(SV2-Pad3)") (class "Default")
      (node (ref "SV2") (pin "3") (pinfunction "3_3") (pintype "passive"))
    )
    (net (code "166") (name "unconnected-(SV2-Pad4)") (class "Default")
      (node (ref "SV2") (pin "4") (pinfunction "4_4") (pintype "passive"))
    )
    (net (code "167") (name "unconnected-(SV2-Pad5)") (class "Default")
      (node (ref "SV2") (pin "5") (pinfunction "5_5") (pintype "passive"))
    )
    (net (code "168") (name "unconnected-(SV2-Pad6)") (class "Default")
      (node (ref "SV2") (pin "6") (pinfunction "6_6") (pintype "passive"))
    )
    (net (code "169") (name "unconnected-(SV2-Pad7)") (class "Default")
      (node (ref "SV2") (pin "7") (pinfunction "7_7") (pintype "passive"))
    )
    (net (code "170") (name "unconnected-(SV2-Pad8)") (class "Default")
      (node (ref "SV2") (pin "8") (pinfunction "8_8") (pintype "passive"))
    )
    (net (code "171") (name "unconnected-(SV2-Pad9)") (class "Default")
      (node (ref "SV2") (pin "9") (pinfunction "9_9") (pintype "passive"))
    )
    (net (code "172") (name "unconnected-(SV2-Pad10)") (class "Default")
      (node (ref "SV2") (pin "10") (pinfunction "10_10") (pintype "passive"))
    )
    (net (code "173") (name "unconnected-(SV2-Pad11)") (class "Default")
      (node (ref "SV2") (pin "11") (pinfunction "11_11") (pintype "passive"))
    )
    (net (code "174") (name "unconnected-(T1-B-Pad2)") (class "Default")
      (node (ref "T1") (pin "2") (pinfunction "B_2") (pintype "passive"))
    )
    (net (code "175") (name "unconnected-(T1-C-Pad3)") (class "Default")
      (node (ref "T1") (pin "3") (pinfunction "C_3") (pintype "passive"))
    )
    (net (code "176") (name "unconnected-(T1-E-Pad1)") (class "Default")
      (node (ref "T1") (pin "1") (pinfunction "E_1") (pintype "passive"))
    )
    (net (code "177") (name "unconnected-(T2-B-Pad2)") (class "Default")
      (node (ref "T2") (pin "2") (pinfunction "B_2") (pintype "passive"))
    )
    (net (code "178") (name "unconnected-(T2-C-Pad3)") (class "Default")
      (node (ref "T2") (pin "3") (pinfunction "C_3") (pintype "passive"))
    )
    (net (code "179") (name "unconnected-(T2-E-Pad1)") (class "Default")
      (node (ref "T2") (pin "1") (pinfunction "E_1") (pintype "passive"))
    )
    (net (code "180") (name "unconnected-(T3-B-Pad2)") (class "Default")
      (node (ref "T3") (pin "2") (pinfunction "B_2") (pintype "passive"))
    )
    (net (code "181") (name "unconnected-(T3-C-Pad3)") (class "Default")
      (node (ref "T3") (pin "3") (pinfunction "C_3") (pintype "passive"))
    )
    (net (code "182") (name "unconnected-(T3-E-Pad1)") (class "Default")
      (node (ref "T3") (pin "1") (pinfunction "E_1") (pintype "passive"))
    )
    (net (code "183") (name "unconnected-(T4-B-Pad2)") (class "Default")
      (node (ref "T4") (pin "2") (pinfunction "B_2") (pintype "passive"))
    )
    (net (code "184") (name "unconnected-(T4-C-Pad3)") (class "Default")
      (node (ref "T4") (pin "3") (pinfunction "C_3") (pintype "passive"))
    )
    (net (code "185") (name "unconnected-(T4-E-Pad1)") (class "Default")
      (node (ref "T4") (pin "1") (pinfunction "E_1") (pintype "passive"))
    )
    (net (code "186") (name "unconnected-(T5-B-Pad2)") (class "Default")
      (node (ref "T5") (pin "2") (pinfunction "B_2") (pintype "passive"))
    )
    (net (code "187") (name "unconnected-(T5-C-Pad3)") (class "Default")
      (node (ref "T5") (pin "3") (pinfunction "C_3") (pintype "passive"))
    )
    (net (code "188") (name "unconnected-(T5-E-Pad1)") (class "Default")
      (node (ref "T5") (pin "1") (pinfunction "E_1") (pintype "passive"))
    )
    (net (code "189") (name "unconnected-(T6-B-Pad2)") (class "Default")
      (node (ref "T6") (pin "2") (pinfunction "B_2") (pintype "passive"))
    )
    (net (code "190") (name "unconnected-(T6-C-Pad3)") (class "Default")
      (node (ref "T6") (pin "3") (pinfunction "C_3") (pintype "passive"))
    )
    (net (code "191") (name "unconnected-(T6-E-Pad1)") (class "Default")
      (node (ref "T6") (pin "1") (pinfunction "E_1") (pintype "passive"))
    )
  )
)
